# mainV2.net
KiCad netlist of a schematic drawn in Altium Designer
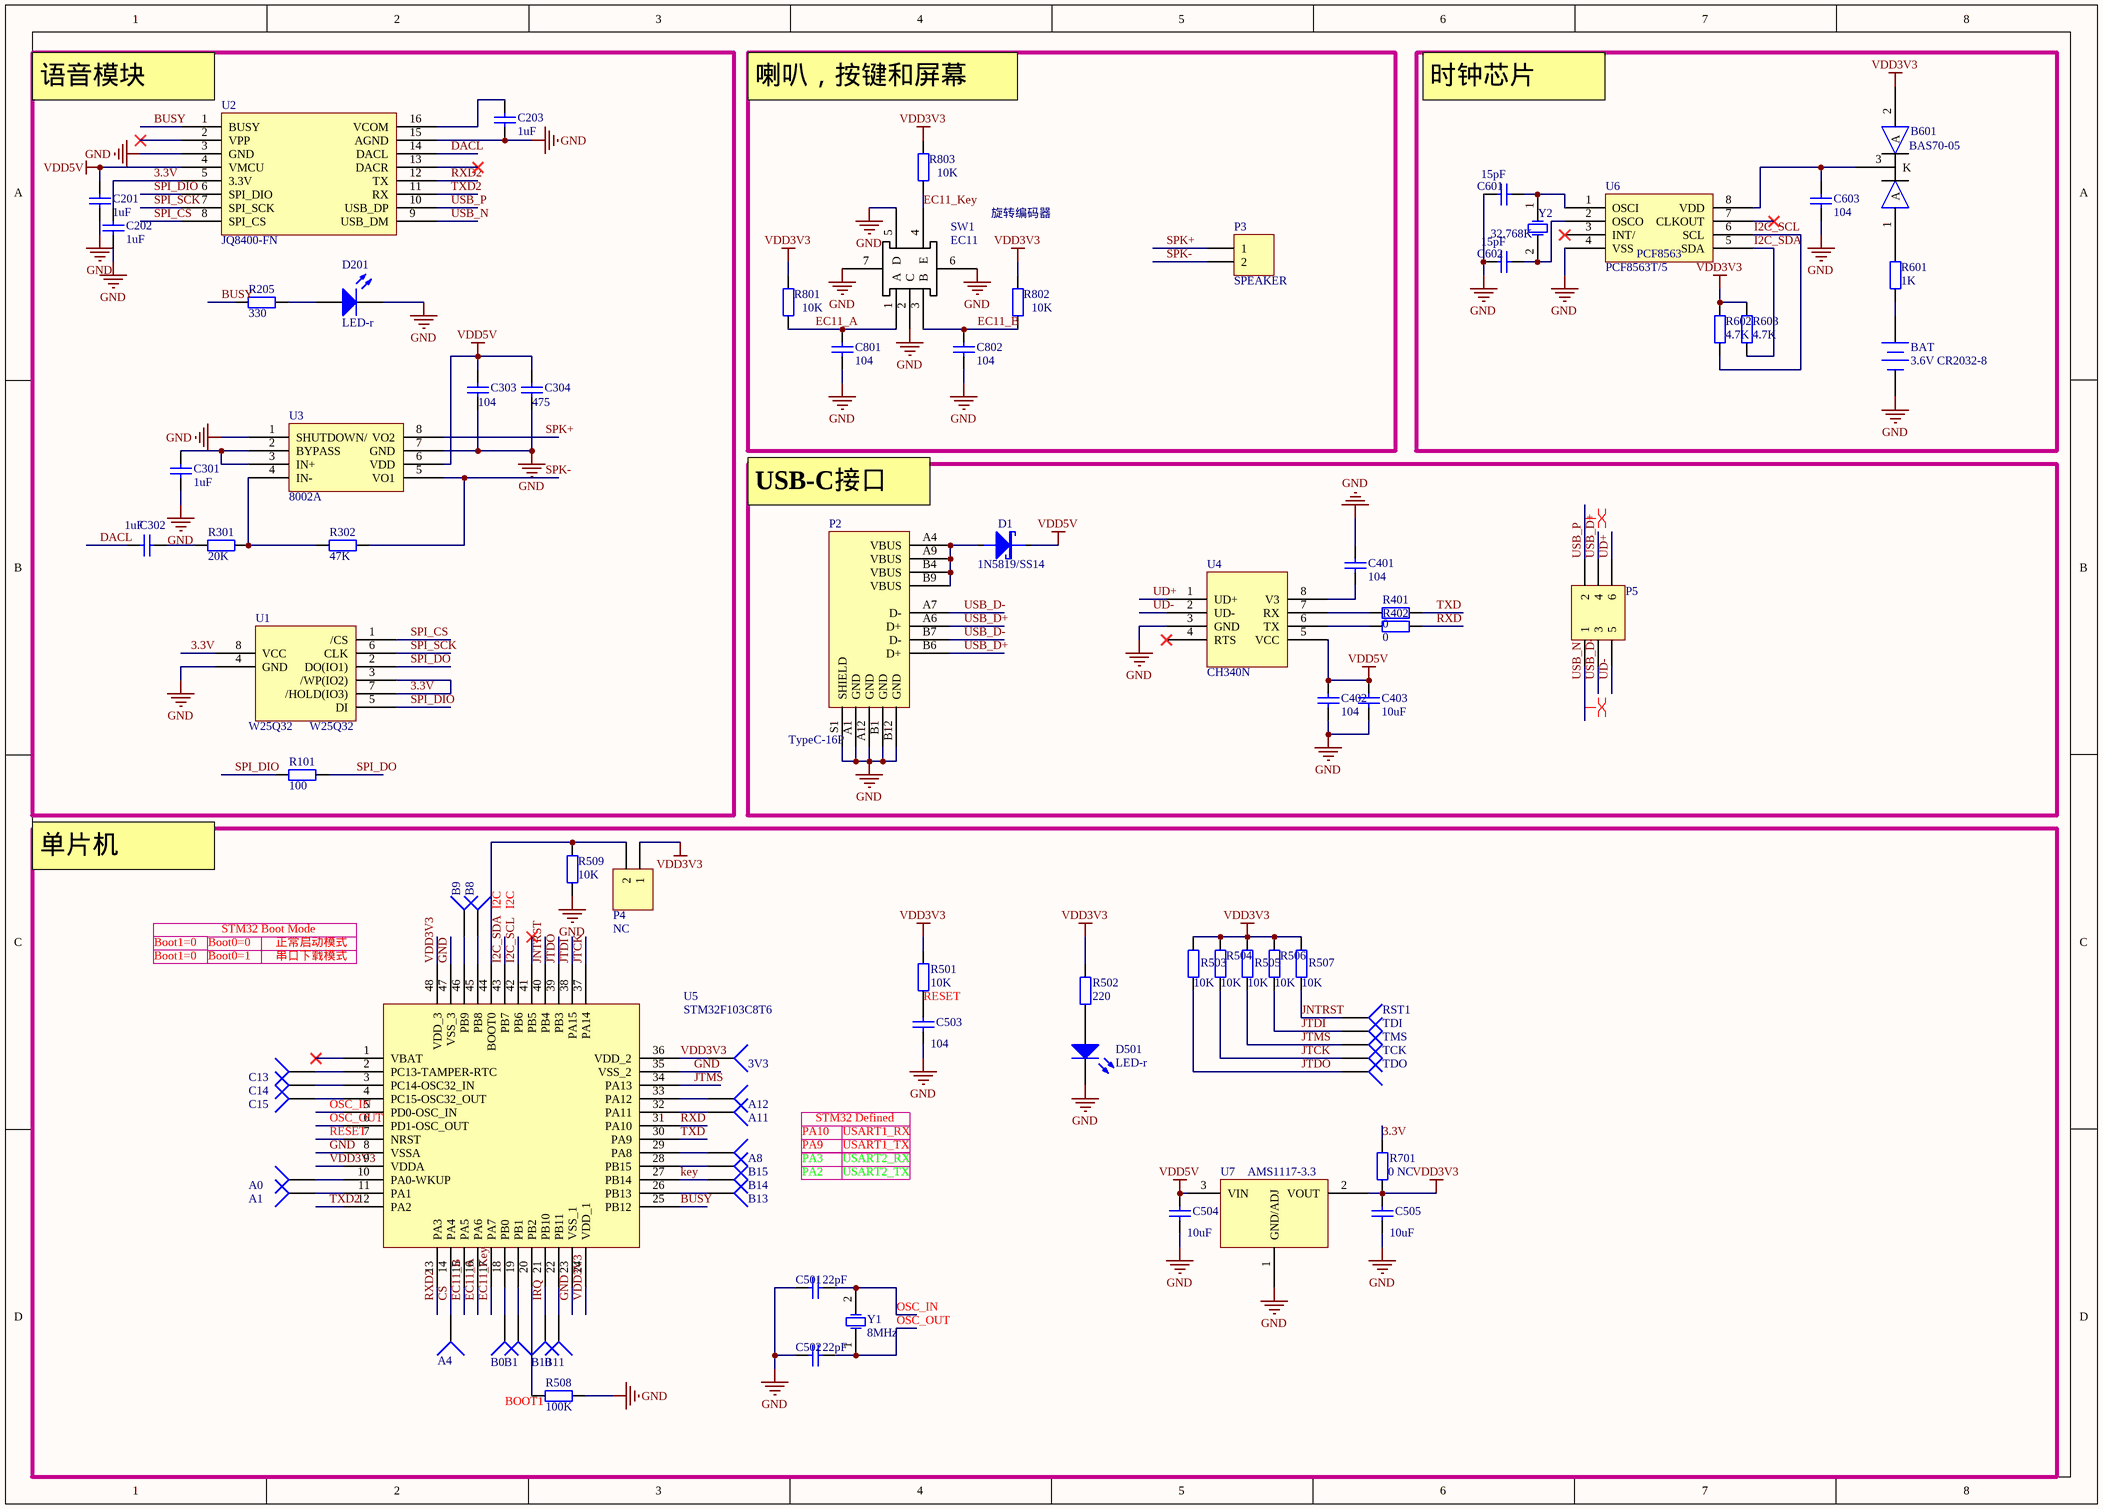
[diagram p0: mainV2.SchDoc]

(export (version "E")
  (design (tool "Eeschema 10.0.6"))
  (components
    (comp (ref "3V3")
      (value "Socket")
      (footprint "TP")
      (fields (field (name "PUBLISHER") "Altium Limited"))
      (libsource (lib "Miscellaneous Connectors") (part "Socket"))
    )
    (comp (ref "A0")
      (value "Socket")
      (footprint "TP")
      (fields (field (name "PUBLISHER") "Altium Limited"))
      (libsource (lib "Miscellaneous Connectors") (part "Socket"))
    )
    (comp (ref "A1")
      (value "Socket")
      (footprint "TP")
      (fields (field (name "PUBLISHER") "Altium Limited"))
      (libsource (lib "Miscellaneous Connectors") (part "Socket"))
    )
    (comp (ref "A4")
      (value "Socket")
      (footprint "TP")
      (fields (field (name "PUBLISHER") "Altium Limited"))
      (libsource (lib "Miscellaneous Connectors") (part "Socket"))
    )
    (comp (ref "A8")
      (value "Socket")
      (footprint "TP")
      (fields (field (name "PUBLISHER") "Altium Limited"))
      (libsource (lib "Miscellaneous Connectors") (part "Socket"))
    )
    (comp (ref "A11")
      (value "Socket")
      (footprint "TP")
      (fields (field (name "PUBLISHER") "Altium Limited"))
      (libsource (lib "Miscellaneous Connectors") (part "Socket"))
    )
    (comp (ref "A12")
      (value "Socket")
      (footprint "TP")
      (fields (field (name "PUBLISHER") "Altium Limited"))
      (libsource (lib "Miscellaneous Connectors") (part "Socket"))
    )
    (comp (ref "B0")
      (value "Socket")
      (footprint "TP")
      (fields (field (name "PUBLISHER") "Altium Limited"))
      (libsource (lib "Miscellaneous Connectors") (part "Socket"))
    )
    (comp (ref "B1")
      (value "Socket")
      (footprint "TP")
      (fields (field (name "PUBLISHER") "Altium Limited"))
      (libsource (lib "Miscellaneous Connectors") (part "Socket"))
    )
    (comp (ref "B8")
      (value "Socket")
      (footprint "TP")
      (fields (field (name "PUBLISHER") "Altium Limited"))
      (libsource (lib "Miscellaneous Connectors") (part "Socket"))
    )
    (comp (ref "B9")
      (value "Socket")
      (footprint "TP")
      (fields (field (name "PUBLISHER") "Altium Limited"))
      (libsource (lib "Miscellaneous Connectors") (part "Socket"))
    )
    (comp (ref "B10")
      (value "Socket")
      (footprint "TP")
      (fields (field (name "PUBLISHER") "Altium Limited"))
      (libsource (lib "Miscellaneous Connectors") (part "Socket"))
    )
    (comp (ref "B11")
      (value "Socket")
      (footprint "TP")
      (fields (field (name "PUBLISHER") "Altium Limited"))
      (libsource (lib "Miscellaneous Connectors") (part "Socket"))
    )
    (comp (ref "B13")
      (value "Socket")
      (footprint "TP")
      (fields (field (name "PUBLISHER") "Altium Limited"))
      (libsource (lib "Miscellaneous Connectors") (part "Socket"))
    )
    (comp (ref "B14")
      (value "Socket")
      (footprint "TP")
      (fields (field (name "PUBLISHER") "Altium Limited"))
      (libsource (lib "Miscellaneous Connectors") (part "Socket"))
    )
    (comp (ref "B15")
      (value "Socket")
      (footprint "TP")
      (fields (field (name "PUBLISHER") "Altium Limited"))
      (libsource (lib "Miscellaneous Connectors") (part "Socket"))
    )
    (comp (ref "B601")
      (value "BAS70-05")
      (footprint "SMT_TRIODE_NPN")
      (description "贴片三极管  丝印75")
      (libsource (lib "Hardware") (part "BAS70 74"))
    )
    (comp (ref "BAT")
      (value "3.6V CR2032-8")
      (footprint "CR2032-8")
      (description "电池座 半圆形")
      (fields (field (name "PUBLISHER") "Altium Limited"))
      (libsource (lib "Miscellaneous Devices") (part "Battery"))
    )
    (comp (ref "C13")
      (value "Socket")
      (footprint "TP")
      (fields (field (name "PUBLISHER") "Altium Limited"))
      (libsource (lib "Miscellaneous Connectors") (part "Socket"))
    )
    (comp (ref "C14")
      (value "Socket")
      (footprint "TP")
      (fields (field (name "PUBLISHER") "Altium Limited"))
      (libsource (lib "Miscellaneous Connectors") (part "Socket"))
    )
    (comp (ref "C15")
      (value "Socket")
      (footprint "TP")
      (fields (field (name "PUBLISHER") "Altium Limited"))
      (libsource (lib "Miscellaneous Connectors") (part "Socket"))
    )
    (comp (ref "C201")
      (value "1uF")
      (footprint "0603_CAP")
      (description "Capacitor 0603")
      (fields (field (name "PUBLISHER") "Altium Limited"))
      (libsource (lib "Miscellaneous Devices") (part "Cap"))
    )
    (comp (ref "C202")
      (value "1uF")
      (footprint "0603_CAP")
      (description "Capacitor 0603")
      (fields (field (name "PUBLISHER") "Altium Limited"))
      (libsource (lib "Miscellaneous Devices") (part "Cap"))
    )
    (comp (ref "C203")
      (value "1uF")
      (footprint "0603_CAP")
      (description "Capacitor 0603")
      (fields (field (name "PUBLISHER") "Altium Limited"))
      (libsource (lib "Miscellaneous Devices") (part "Cap"))
    )
    (comp (ref "C301")
      (value "1uF")
      (footprint "0603_CAP")
      (description "Capacitor 0603")
      (fields (field (name "PUBLISHER") "Altium Limited"))
      (libsource (lib "Miscellaneous Devices") (part "Cap"))
    )
    (comp (ref "C302")
      (value "1uF")
      (footprint "0603_CAP")
      (description "Capacitor 0603")
      (fields (field (name "PUBLISHER") "Altium Limited"))
      (libsource (lib "Miscellaneous Devices") (part "Cap"))
    )
    (comp (ref "C303")
      (value "104")
      (footprint "0603_CAP")
      (description "Capacitor 0603")
      (fields (field (name "PUBLISHER") "Altium Limited"))
      (libsource (lib "Miscellaneous Devices") (part "Cap"))
    )
    (comp (ref "C304")
      (value "475")
      (footprint "0603_CAP")
      (description "Capacitor 0603")
      (fields (field (name "PUBLISHER") "Altium Limited"))
      (libsource (lib "Miscellaneous Devices") (part "Cap"))
    )
    (comp (ref "C401")
      (value "104")
      (footprint "0603_CAP")
      (description "Capacitor 0603")
      (fields (field (name "PUBLISHER") "Altium Limited"))
      (libsource (lib "Miscellaneous Devices") (part "Cap"))
    )
    (comp (ref "C402")
      (value "104")
      (footprint "0603_CAP")
      (description "Capacitor 0603")
      (fields (field (name "PUBLISHER") "Altium Limited"))
      (libsource (lib "Miscellaneous Devices") (part "Cap"))
    )
    (comp (ref "C403")
      (value "10uF")
      (footprint "0603_CAP")
      (description "Capacitor 0603")
      (fields (field (name "PUBLISHER") "Altium Limited"))
      (libsource (lib "Miscellaneous Devices") (part "Cap"))
    )
    (comp (ref "C501")
      (value "22pF")
      (footprint "0603_CAP")
      (description "Capacitor 0603")
      (fields (field (name "PUBLISHER") "Altium Limited"))
      (libsource (lib "Miscellaneous Devices") (part "Cap"))
    )
    (comp (ref "C502")
      (value "22pF")
      (footprint "0603_CAP")
      (description "Capacitor 0603")
      (fields (field (name "PUBLISHER") "Altium Limited"))
      (libsource (lib "Miscellaneous Devices") (part "Cap"))
    )
    (comp (ref "C503")
      (value "104")
      (footprint "0603_CAP")
      (description "Capacitor 0603")
      (fields (field (name "PUBLISHER") "Altium Limited"))
      (libsource (lib "Miscellaneous Devices") (part "Cap"))
    )
    (comp (ref "C504")
      (value "10uF")
      (footprint "0603_CAP")
      (description "Capacitor 0603")
      (fields (field (name "PUBLISHER") "Altium Limited"))
      (libsource (lib "Miscellaneous Devices") (part "Cap"))
    )
    (comp (ref "C505")
      (value "10uF")
      (footprint "0603_CAP")
      (description "Capacitor 0603")
      (fields (field (name "PUBLISHER") "Altium Limited"))
      (libsource (lib "Miscellaneous Devices") (part "Cap"))
    )
    (comp (ref "C601")
      (value "15pF")
      (footprint "0603_CAP")
      (description "Capacitor 0603")
      (fields (field (name "PUBLISHER") "Altium Limited"))
      (libsource (lib "Miscellaneous Devices") (part "Cap"))
    )
    (comp (ref "C602")
      (value "15pF")
      (footprint "0603_CAP")
      (description "Capacitor 0603")
      (fields (field (name "PUBLISHER") "Altium Limited"))
      (libsource (lib "Miscellaneous Devices") (part "Cap"))
    )
    (comp (ref "C603")
      (value "104")
      (footprint "0603_CAP")
      (description "Capacitor 0603")
      (fields (field (name "PUBLISHER") "Altium Limited"))
      (libsource (lib "Miscellaneous Devices") (part "Cap"))
    )
    (comp (ref "C801")
      (value "104")
      (footprint "0603_CAP")
      (description "Capacitor 0603")
      (fields (field (name "PUBLISHER") "Altium Limited"))
      (libsource (lib "Miscellaneous Devices") (part "Cap"))
    )
    (comp (ref "C802")
      (value "104")
      (footprint "0603_CAP")
      (description "Capacitor 0603")
      (fields (field (name "PUBLISHER") "Altium Limited"))
      (libsource (lib "Miscellaneous Devices") (part "Cap"))
    )
    (comp (ref "D1")
      (value "1N5819/SS14")
      (footprint "SMA")
      (description "肖特基整流二极管SOD-323")
      (libsource (lib "Vowstar_Basic_Device") (part "SMT_DIODE_SCHOTTKY_SOD_323"))
    )
    (comp (ref "D201")
      (value "LED-r")
      (footprint "LED-0603")
      (description "NC")
      (fields (field (name "PUBLISHER") "Altium Limited"))
      (libsource (lib "Miscellaneous Devices") (part "LED2"))
    )
    (comp (ref "D501")
      (value "LED-r")
      (footprint "LED-0603")
      (description "NC")
      (fields (field (name "PUBLISHER") "Altium Limited"))
      (libsource (lib "Miscellaneous Devices") (part "LED2"))
    )
    (comp (ref "P2")
      (value "TypeC-16P")
      (footprint "type-c 16pin")
      (libsource (lib "Hardware") (part "TypeC-16P"))
    )
    (comp (ref "P3")
      (value "SPEAKER")
      (footprint "Speaker")
      (description "扬声器")
      (fields (field (name "PUBLISHER") "Altium Limited"))
      (libsource (lib "") (part "Header 2_1"))
    )
    (comp (ref "P4")
      (value "NC")
      (footprint "HDR1X2")
      (description "下载短接口")
      (fields (field (name "PUBLISHER") "Altium Limited"))
      (libsource (lib "Miscellaneous Connectors") (part "Header 2"))
    )
    (comp (ref "P5")
      (value "NC 3X2")
      (footprint "HDR2X3")
      (description "USB跳线接口")
      (fields (field (name "PUBLISHER") "Altium Limited"))
      (libsource (lib "Miscellaneous Connectors") (part "Header 3X2"))
    )
    (comp (ref "R101")
      (value "100")
      (footprint "0603_CAP")
      (description "Resistor 0603")
      (fields (field (name "PUBLISHER") "Altium Limited"))
      (libsource (lib "") (part "Res2_1"))
    )
    (comp (ref "R205")
      (value "330")
      (footprint "0603_CAP")
      (description "Resistor 0603")
      (fields (field (name "PUBLISHER") "Altium Limited"))
      (libsource (lib "") (part "Res2_1"))
    )
    (comp (ref "R301")
      (value "20K")
      (footprint "0603_CAP")
      (description "Resistor 0603")
      (fields (field (name "PUBLISHER") "Altium Limited"))
      (libsource (lib "") (part "Res2_1"))
    )
    (comp (ref "R302")
      (value "47K")
      (footprint "0603_CAP")
      (description "Resistor 0603")
      (fields (field (name "PUBLISHER") "Altium Limited"))
      (libsource (lib "") (part "Res2_1"))
    )
    (comp (ref "R401")
      (value "0")
      (footprint "0603_CAP")
      (description "Resistor 0603")
      (fields (field (name "PUBLISHER") "Altium Limited"))
      (libsource (lib "") (part "Res2_3"))
    )
    (comp (ref "R402")
      (value "0")
      (footprint "0603_CAP")
      (description "Resistor 0603")
      (fields (field (name "PUBLISHER") "Altium Limited"))
      (libsource (lib "") (part "Res2_3"))
    )
    (comp (ref "R501")
      (value "10K")
      (footprint "0603_CAP")
      (description "Resistor 0603")
      (fields (field (name "PUBLISHER") "Altium Limited"))
      (libsource (lib "") (part "Res2_2"))
    )
    (comp (ref "R502")
      (value "220")
      (footprint "0603_CAP")
      (description "Resistor 0603")
      (fields (field (name "PUBLISHER") "Altium Limited"))
      (libsource (lib "") (part "Res2_2"))
    )
    (comp (ref "R503")
      (value "10K")
      (footprint "0603_CAP")
      (description "Resistor 0603")
      (fields (field (name "PUBLISHER") "Altium Limited"))
      (libsource (lib "") (part "Res2_2"))
    )
    (comp (ref "R504")
      (value "10K")
      (footprint "0603_CAP")
      (description "Resistor 0603")
      (fields (field (name "PUBLISHER") "Altium Limited"))
      (libsource (lib "") (part "Res2_2"))
    )
    (comp (ref "R505")
      (value "10K")
      (footprint "0603_CAP")
      (description "Resistor 0603")
      (fields (field (name "PUBLISHER") "Altium Limited"))
      (libsource (lib "") (part "Res2_2"))
    )
    (comp (ref "R506")
      (value "10K")
      (footprint "0603_CAP")
      (description "Resistor 0603")
      (fields (field (name "PUBLISHER") "Altium Limited"))
      (libsource (lib "") (part "Res2_2"))
    )
    (comp (ref "R507")
      (value "10K")
      (footprint "0603_CAP")
      (description "Resistor 0603")
      (fields (field (name "PUBLISHER") "Altium Limited"))
      (libsource (lib "") (part "Res2_2"))
    )
    (comp (ref "R508")
      (value "100K")
      (footprint "0603_CAP")
      (description "Resistor 0603")
      (fields (field (name "PUBLISHER") "Altium Limited"))
      (libsource (lib "") (part "Res2_3"))
    )
    (comp (ref "R509")
      (value "10K")
      (footprint "0603_CAP")
      (description "Resistor 0603")
      (fields (field (name "PUBLISHER") "Altium Limited"))
      (libsource (lib "") (part "Res2_2"))
    )
    (comp (ref "R601")
      (value "1K")
      (footprint "0603_CAP")
      (description "Resistor 0603")
      (fields (field (name "PUBLISHER") "Altium Limited"))
      (libsource (lib "") (part "Res2_2"))
    )
    (comp (ref "R602")
      (value "4.7K")
      (footprint "0603_CAP")
      (description "Resistor 0603")
      (fields (field (name "PUBLISHER") "Altium Limited"))
      (libsource (lib "") (part "Res2_2"))
    )
    (comp (ref "R603")
      (value "4.7K")
      (footprint "0603_CAP")
      (description "Resistor 0603")
      (fields (field (name "PUBLISHER") "Altium Limited"))
      (libsource (lib "") (part "Res2_2"))
    )
    (comp (ref "R701")
      (value "0 NC")
      (footprint "0603_CAP")
      (description "Resistor 0603")
      (fields (field (name "PUBLISHER") "Altium Limited"))
      (libsource (lib "") (part "Res2_2"))
    )
    (comp (ref "R801")
      (value "10K")
      (footprint "0603_CAP")
      (description "Resistor 0603")
      (fields (field (name "PUBLISHER") "Altium Limited"))
      (libsource (lib "Miscellaneous Devices") (part "Res2"))
    )
    (comp (ref "R802")
      (value "10K")
      (footprint "0603_CAP")
      (description "Resistor 0603")
      (fields (field (name "PUBLISHER") "Altium Limited"))
      (libsource (lib "Miscellaneous Devices") (part "Res2"))
    )
    (comp (ref "R803")
      (value "10K")
      (footprint "0603_CAP")
      (description "Resistor 0603")
      (fields (field (name "PUBLISHER") "Altium Limited"))
      (libsource (lib "Miscellaneous Devices") (part "Res2"))
    )
    (comp (ref "RST1")
      (value "Socket")
      (footprint "TP")
      (fields (field (name "PUBLISHER") "Altium Limited"))
      (libsource (lib "Miscellaneous Connectors") (part "Socket"))
    )
    (comp (ref "SW1")
      (value "EC11")
      (footprint "EC11")
      (description "旋转编码器20脉冲")
      (libsource (lib "Hardware") (part "EC11"))
    )
    (comp (ref "TCK")
      (value "Socket")
      (footprint "TP")
      (fields (field (name "PUBLISHER") "Altium Limited"))
      (libsource (lib "Miscellaneous Connectors") (part "Socket"))
    )
    (comp (ref "TDI")
      (value "Socket")
      (footprint "TP")
      (fields (field (name "PUBLISHER") "Altium Limited"))
      (libsource (lib "Miscellaneous Connectors") (part "Socket"))
    )
    (comp (ref "TDO")
      (value "Socket")
      (footprint "TP")
      (fields (field (name "PUBLISHER") "Altium Limited"))
      (libsource (lib "Miscellaneous Connectors") (part "Socket"))
    )
    (comp (ref "TMS")
      (value "Socket")
      (footprint "TP")
      (fields (field (name "PUBLISHER") "Altium Limited"))
      (libsource (lib "Miscellaneous Connectors") (part "Socket"))
    )
    (comp (ref "U1")
      (value "W25Q32")
      (footprint "SOP8-208mil")
      (description "Flash")
      (libsource (lib "Hardware") (part "W25Q32"))
    )
    (comp (ref "U2")
      (value "JQ8400-FN")
      (footprint "JQF8400-FL")
      (libsource (lib "Hardware") (part "JQ8400-FN"))
    )
    (comp (ref "U3")
      (value "8002A")
      (footprint "8002A")
      (description "3W功放")
      (libsource (lib "Hardware") (part "8002A"))
    )
    (comp (ref "U4")
      (value "CH340N")
      (footprint "SOP8")
      (description "U转串")
      (libsource (lib "clock") (part "ch340"))
    )
    (comp (ref "U5")
      (value "STM32F103C8T6")
      (footprint "LQFP48")
      (description "单片机")
      (libsource (lib "Hardware") (part "STM32F101CB"))
    )
    (comp (ref "U6")
      (value "PCF8563T/5")
      (footprint "PCF8563")
      (description "时钟芯片")
      (libsource (lib "Hardware") (part "PCF8563"))
    )
    (comp (ref "U7")
      (value "AMS1117-3.3")
      (footprint "SOT-223")
      (libsource (lib "Vowstar_IC_General") (part "NCP1117"))
    )
    (comp (ref "Y1")
      (value "8MHz")
      (footprint "HC-49SMD")
      (description "49S型直插无源晶振")
      (fields (field (name "PUBLISHER") "Altium Limited"))
      (libsource (lib "Miscellaneous Devices") (part "XTAL"))
    )
    (comp (ref "Y2")
      (value "32.768K")
      (footprint "Crystal")
      (description "圆柱型3*8mm无源晶振")
      (fields (field (name "PUBLISHER") "Altium Limited"))
      (libsource (lib "Miscellaneous Devices") (part "XTAL"))
    )
  )
  (nets
    (net (code "1") (name "/3.3V") (class "Default")
      (node (ref "C202") (pin "2") (pinfunction "2_2") (pintype "passive"))
      (node (ref "R701") (pin "2") (pinfunction "2_2") (pintype "passive"))
      (node (ref "U1") (pin "3") (pinfunction "/WP(IO2)_3") (pintype "passive"))
      (node (ref "U1") (pin "7") (pinfunction "/HOLD(IO3)_7") (pintype "passive"))
      (node (ref "U1") (pin "8") (pinfunction "VCC_8") (pintype "passive"))
      (node (ref "U2") (pin "5") (pinfunction "3.3V_5") (pintype "passive"))
    )
    (net (code "2") (name "/BUSY") (class "Default")
      (node (ref "R205") (pin "2") (pinfunction "2_2") (pintype "passive"))
      (node (ref "U2") (pin "1") (pinfunction "BUSY_1") (pintype "passive"))
      (node (ref "U5") (pin "25") (pinfunction "PB12_25") (pintype "passive"))
    )
    (net (code "3") (name "/CS") (class "Default")
      (node (ref "A4") (pin "1") (pinfunction "1_1") (pintype "passive"))
      (node (ref "U5") (pin "14") (pinfunction "PA4_14") (pintype "passive"))
    )
    (net (code "4") (name "/DACL") (class "Default")
      (node (ref "C302") (pin "2") (pinfunction "2_2") (pintype "passive"))
      (node (ref "U2") (pin "14") (pinfunction "DACL_14") (pintype "passive"))
    )
    (net (code "5") (name "/EC11_A") (class "Default")
      (node (ref "C801") (pin "1") (pinfunction "1_1") (pintype "passive"))
      (node (ref "R801") (pin "2") (pinfunction "2_2") (pintype "passive"))
      (node (ref "SW1") (pin "1") (pinfunction "A_1") (pintype "passive"))
      (node (ref "U5") (pin "16") (pinfunction "PA6_16") (pintype "passive"))
    )
    (net (code "6") (name "/EC11_B") (class "Default")
      (node (ref "C802") (pin "1") (pinfunction "1_1") (pintype "passive"))
      (node (ref "R802") (pin "2") (pinfunction "2_2") (pintype "passive"))
      (node (ref "SW1") (pin "3") (pinfunction "B_3") (pintype "passive"))
      (node (ref "U5") (pin "15") (pinfunction "PA5_15") (pintype "passive"))
    )
    (net (code "7") (name "/EC11_Key") (class "Default")
      (node (ref "R803") (pin "2") (pinfunction "2_2") (pintype "passive"))
      (node (ref "SW1") (pin "4") (pinfunction "E_4") (pintype "passive"))
      (node (ref "U5") (pin "17") (pinfunction "PA7_17") (pintype "passive"))
    )
    (net (code "8") (name "/I2C_SCL") (class "Default")
      (node (ref "R602") (pin "1") (pinfunction "1_1") (pintype "passive"))
      (node (ref "U5") (pin "42") (pinfunction "PB6_42") (pintype "passive"))
      (node (ref "U6") (pin "6") (pinfunction "SCL_6") (pintype "passive"))
    )
    (net (code "9") (name "/I2C_SDA") (class "Default")
      (node (ref "R603") (pin "1") (pinfunction "1_1") (pintype "passive"))
      (node (ref "U5") (pin "43") (pinfunction "PB7_43") (pintype "passive"))
      (node (ref "U6") (pin "5") (pinfunction "SDA_5") (pintype "passive"))
    )
    (net (code "10") (name "/IRQ") (class "Default")
      (node (ref "B10") (pin "1") (pinfunction "1_1") (pintype "passive"))
      (node (ref "U5") (pin "21") (pinfunction "PB10_21") (pintype "passive"))
    )
    (net (code "11") (name "/JNTRST") (class "Default")
      (node (ref "R507") (pin "1") (pinfunction "1_1") (pintype "passive"))
      (node (ref "RST1") (pin "1") (pinfunction "1_1") (pintype "passive"))
      (node (ref "U5") (pin "40") (pinfunction "PB4_40") (pintype "passive"))
    )
    (net (code "12") (name "/JTCK") (class "Default")
      (node (ref "R504") (pin "1") (pinfunction "1_1") (pintype "passive"))
      (node (ref "TCK") (pin "1") (pinfunction "1_1") (pintype "passive"))
      (node (ref "U5") (pin "37") (pinfunction "PA14_37") (pintype "passive"))
    )
    (net (code "13") (name "/JTDI") (class "Default")
      (node (ref "R506") (pin "1") (pinfunction "1_1") (pintype "passive"))
      (node (ref "TDI") (pin "1") (pinfunction "1_1") (pintype "passive"))
      (node (ref "U5") (pin "38") (pinfunction "PA15_38") (pintype "passive"))
    )
    (net (code "14") (name "/JTDO") (class "Default")
      (node (ref "R503") (pin "1") (pinfunction "1_1") (pintype "passive"))
      (node (ref "TDO") (pin "1") (pinfunction "1_1") (pintype "passive"))
      (node (ref "U5") (pin "39") (pinfunction "PB3_39") (pintype "passive"))
    )
    (net (code "15") (name "/JTMS") (class "Default")
      (node (ref "R505") (pin "1") (pinfunction "1_1") (pintype "passive"))
      (node (ref "TMS") (pin "1") (pinfunction "1_1") (pintype "passive"))
      (node (ref "U5") (pin "34") (pinfunction "PA13_34") (pintype "passive"))
    )
    (net (code "16") (name "/OSC_IN") (class "Default")
      (node (ref "C501") (pin "1") (pinfunction "1_1") (pintype "passive"))
      (node (ref "U5") (pin "5") (pinfunction "PD0-OSC_IN_5") (pintype "passive"))
      (node (ref "Y1") (pin "2") (pinfunction "OSC2_2") (pintype "passive"))
    )
    (net (code "17") (name "/OSC_OUT") (class "Default")
      (node (ref "C502") (pin "1") (pinfunction "1_1") (pintype "passive"))
      (node (ref "U5") (pin "6") (pinfunction "PD1-OSC_OUT_6") (pintype "passive"))
      (node (ref "Y1") (pin "1") (pinfunction "OSC1_1") (pintype "passive"))
    )
    (net (code "18") (name "/RESET") (class "Default")
      (node (ref "C503") (pin "1") (pinfunction "1_1") (pintype "passive"))
      (node (ref "R501") (pin "1") (pinfunction "1_1") (pintype "passive"))
      (node (ref "U5") (pin "7") (pinfunction "NRST_7") (pintype "passive"))
    )
    (net (code "19") (name "/RXD") (class "Default")
      (node (ref "R402") (pin "2") (pinfunction "2_2") (pintype "passive"))
      (node (ref "U5") (pin "31") (pinfunction "PA10_31") (pintype "passive"))
    )
    (net (code "20") (name "/RXD2") (class "Default")
      (node (ref "U2") (pin "12") (pinfunction "TX_12") (pintype "passive"))
      (node (ref "U5") (pin "13") (pinfunction "PA3_13") (pintype "passive"))
    )
    (net (code "21") (name "/SPI_CS") (class "Default")
      (node (ref "U1") (pin "1") (pinfunction "/CS_1") (pintype "passive"))
      (node (ref "U2") (pin "8") (pinfunction "SPI_CS_8") (pintype "passive"))
    )
    (net (code "22") (name "/SPI_DIO") (class "Default")
      (node (ref "R101") (pin "2") (pinfunction "2_2") (pintype "passive"))
      (node (ref "U1") (pin "5") (pinfunction "DI_5") (pintype "passive"))
      (node (ref "U2") (pin "6") (pinfunction "SPI_DIO_6") (pintype "passive"))
    )
    (net (code "23") (name "/SPI_DO") (class "Default")
      (node (ref "R101") (pin "1") (pinfunction "1_1") (pintype "passive"))
      (node (ref "U1") (pin "2") (pinfunction "DO(IO1)_2") (pintype "passive"))
    )
    (net (code "24") (name "/SPI_SCK") (class "Default")
      (node (ref "U1") (pin "6") (pinfunction "CLK_6") (pintype "passive"))
      (node (ref "U2") (pin "7") (pinfunction "SPI_SCK_7") (pintype "passive"))
    )
    (net (code "25") (name "/SPK+") (class "Default")
      (node (ref "P3") (pin "1") (pinfunction "1_1") (pintype "passive"))
      (node (ref "U3") (pin "8") (pinfunction "VO2_8") (pintype "passive"))
    )
    (net (code "26") (name "/SPK-") (class "Default")
      (node (ref "P3") (pin "2") (pinfunction "2_2") (pintype "passive"))
      (node (ref "R302") (pin "1") (pinfunction "1_1") (pintype "passive"))
      (node (ref "U3") (pin "5") (pinfunction "VO1_5") (pintype "passive"))
    )
    (net (code "27") (name "/TXD") (class "Default")
      (node (ref "R401") (pin "2") (pinfunction "2_2") (pintype "passive"))
      (node (ref "U5") (pin "30") (pinfunction "PA9_30") (pintype "passive"))
    )
    (net (code "28") (name "/TXD2") (class "Default")
      (node (ref "U2") (pin "11") (pinfunction "RX_11") (pintype "passive"))
      (node (ref "U5") (pin "12") (pinfunction "PA2_12") (pintype "passive"))
    )
    (net (code "29") (name "/UD+") (class "Default")
      (node (ref "P5") (pin "6") (pinfunction "6_6") (pintype "passive"))
      (node (ref "U4") (pin "1") (pinfunction "UD+_1") (pintype "passive"))
    )
    (net (code "30") (name "/UD-") (class "Default")
      (node (ref "P5") (pin "5") (pinfunction "5_5") (pintype "passive"))
      (node (ref "U4") (pin "2") (pinfunction "UD-_2") (pintype "passive"))
    )
    (net (code "31") (name "/USB_D+") (class "Default")
      (node (ref "P2") (pin "A6") (pinfunction "D+_A6") (pintype "passive"))
      (node (ref "P2") (pin "B6") (pinfunction "D+_B6") (pintype "passive"))
      (node (ref "P5") (pin "4") (pinfunction "4_4") (pintype "passive"))
    )
    (net (code "32") (name "/USB_D-") (class "Default")
      (node (ref "P2") (pin "A7") (pinfunction "D-_A7") (pintype "passive"))
      (node (ref "P2") (pin "B7") (pinfunction "D-_B7") (pintype "passive"))
      (node (ref "P5") (pin "3") (pinfunction "3_3") (pintype "passive"))
    )
    (net (code "33") (name "/USB_N") (class "Default")
      (node (ref "P5") (pin "1") (pinfunction "1_1") (pintype "passive"))
      (node (ref "U2") (pin "9") (pinfunction "USB_DM_9") (pintype "passive"))
    )
    (net (code "34") (name "/USB_P") (class "Default")
      (node (ref "P5") (pin "2") (pinfunction "2_2") (pintype "passive"))
      (node (ref "U2") (pin "10") (pinfunction "USB_DP_10") (pintype "passive"))
    )
    (net (code "35") (name "/key") (class "Default")
      (node (ref "B14") (pin "1") (pinfunction "1_1") (pintype "passive"))
      (node (ref "U5") (pin "27") (pinfunction "PB14_27") (pintype "passive"))
    )
    (net (code "36") (name "GND") (class "Default")
      (node (ref "BAT") (pin "2") (pinfunction "-_2") (pintype "passive"))
      (node (ref "C201") (pin "1") (pinfunction "1_1") (pintype "passive"))
      (node (ref "C202") (pin "1") (pinfunction "1_1") (pintype "passive"))
      (node (ref "C203") (pin "2") (pinfunction "2_2") (pintype "passive"))
      (node (ref "C301") (pin "1") (pinfunction "1_1") (pintype "passive"))
      (node (ref "C303") (pin "2") (pinfunction "2_2") (pintype "passive"))
      (node (ref "C304") (pin "2") (pinfunction "2_2") (pintype "passive"))
      (node (ref "C401") (pin "2") (pinfunction "2_2") (pintype "passive"))
      (node (ref "C402") (pin "1") (pinfunction "1_1") (pintype "passive"))
      (node (ref "C403") (pin "1") (pinfunction "1_1") (pintype "passive"))
      (node (ref "C501") (pin "2") (pinfunction "2_2") (pintype "passive"))
      (node (ref "C502") (pin "2") (pinfunction "2_2") (pintype "passive"))
      (node (ref "C503") (pin "2") (pinfunction "2_2") (pintype "passive"))
      (node (ref "C504") (pin "2") (pinfunction "2_2") (pintype "passive"))
      (node (ref "C505") (pin "2") (pinfunction "2_2") (pintype "passive"))
      (node (ref "C601") (pin "2") (pinfunction "2_2") (pintype "passive"))
      (node (ref "C602") (pin "2") (pinfunction "2_2") (pintype "passive"))
      (node (ref "C603") (pin "2") (pinfunction "2_2") (pintype "passive"))
      (node (ref "C801") (pin "2") (pinfunction "2_2") (pintype "passive"))
      (node (ref "C802") (pin "2") (pinfunction "2_2") (pintype "passive"))
      (node (ref "D201") (pin "2") (pinfunction "K_2") (pintype "passive"))
      (node (ref "D501") (pin "2") (pinfunction "K_2") (pintype "passive"))
      (node (ref "P2") (pin "A1") (pinfunction "GND_A1") (pintype "passive"))
      (node (ref "P2") (pin "A12") (pinfunction "GND_A12") (pintype "passive"))
      (node (ref "P2") (pin "B1") (pinfunction "GND_B1") (pintype "passive"))
      (node (ref "P2") (pin "B12") (pinfunction "GND_B12") (pintype "passive"))
      (node (ref "P2") (pin "S1") (pinfunction "SHIELD_S1") (pintype "passive"))
      (node (ref "R508") (pin "2") (pinfunction "2_2") (pintype "passive"))
      (node (ref "R509") (pin "1") (pinfunction "1_1") (pintype "passive"))
      (node (ref "SW1") (pin "2") (pinfunction "C_2") (pintype "passive"))
      (node (ref "SW1") (pin "5") (pinfunction "D_5") (pintype "passive"))
      (node (ref "SW1") (pin "6") (pinfunction "6_6") (pintype "passive"))
      (node (ref "SW1") (pin "7") (pinfunction "7_7") (pintype "passive"))
      (node (ref "U1") (pin "4") (pinfunction "GND_4") (pintype "passive"))
      (node (ref "U2") (pin "15") (pinfunction "AGND_15") (pintype "passive"))
      (node (ref "U2") (pin "3") (pinfunction "GND_3") (pintype "passive"))
      (node (ref "U3") (pin "1") (pinfunction "SHUTDOWN/_1") (pintype "passive"))
      (node (ref "U3") (pin "7") (pinfunction "GND_7") (pintype "passive"))
      (node (ref "U4") (pin "3") (pinfunction "GND_3") (pintype "passive"))
      (node (ref "U5") (pin "23") (pinfunction "VSS_1_23") (pintype "passive"))
      (node (ref "U5") (pin "35") (pinfunction "VSS_2_35") (pintype "passive"))
      (node (ref "U5") (pin "47") (pinfunction "VSS_3_47") (pintype "passive"))
      (node (ref "U5") (pin "8") (pinfunction "VSSA_8") (pintype "passive"))
      (node (ref "U6") (pin "4") (pinfunction "VSS_4") (pintype "passive"))
      (node (ref "U7") (pin "1") (pinfunction "GND/ADJ_1") (pintype "passive"))
    )
    (net (code "37") (name "Net-(B601-A-Pad1)") (class "Default")
      (node (ref "B601") (pin "1") (pinfunction "A_1") (pintype "passive"))
      (node (ref "R601") (pin "2") (pinfunction "2_2") (pintype "passive"))
    )
    (net (code "38") (name "Net-(B601-K)") (class "Default")
      (node (ref "B601") (pin "3") (pinfunction "K_3") (pintype "passive"))
      (node (ref "C603") (pin "1") (pinfunction "1_1") (pintype "passive"))
      (node (ref "U6") (pin "8") (pinfunction "VDD_8") (pintype "passive"))
    )
    (net (code "39") (name "Net-(BAT-+)") (class "Default")
      (node (ref "BAT") (pin "1") (pinfunction "+_1") (pintype "passive"))
      (node (ref "R601") (pin "1") (pinfunction "1_1") (pintype "passive"))
    )
    (net (code "40") (name "Net-(C302-Pad1)") (class "Default")
      (node (ref "C302") (pin "1") (pinfunction "1_1") (pintype "passive"))
      (node (ref "R301") (pin "2") (pinfunction "2_2") (pintype "passive"))
    )
    (net (code "41") (name "Net-(D1-A)") (class "Default")
      (node (ref "D1") (pin "1") (pinfunction "A_1") (pintype "passive"))
      (node (ref "P2") (pin "A4") (pinfunction "VBUS_A4") (pintype "passive"))
      (node (ref "P2") (pin "A9") (pinfunction "VBUS_A9") (pintype "passive"))
      (node (ref "P2") (pin "B4") (pinfunction "VBUS_B4") (pintype "passive"))
      (node (ref "P2") (pin "B9") (pinfunction "VBUS_B9") (pintype "passive"))
    )
    (net (code "42") (name "Net-(D201-A)") (class "Default")
      (node (ref "D201") (pin "1") (pinfunction "A_1") (pintype "passive"))
      (node (ref "R205") (pin "1") (pinfunction "1_1") (pintype "passive"))
    )
    (net (code "43") (name "Net-(D501-A)") (class "Default")
      (node (ref "D501") (pin "1") (pinfunction "A_1") (pintype "passive"))
      (node (ref "R502") (pin "1") (pinfunction "1_1") (pintype "passive"))
    )
    (net (code "44") (name "Net-(U2-VCOM)") (class "Default")
      (node (ref "C203") (pin "1") (pinfunction "1_1") (pintype "passive"))
      (node (ref "U2") (pin "16") (pinfunction "VCOM_16") (pintype "passive"))
    )
    (net (code "45") (name "Net-(U3-BYPASS)") (class "Default")
      (node (ref "C301") (pin "2") (pinfunction "2_2") (pintype "passive"))
      (node (ref "U3") (pin "2") (pinfunction "BYPASS_2") (pintype "passive"))
      (node (ref "U3") (pin "3") (pinfunction "IN+_3") (pintype "passive"))
    )
    (net (code "46") (name "Net-(U3-IN-)") (class "Default")
      (node (ref "R301") (pin "1") (pinfunction "1_1") (pintype "passive"))
      (node (ref "R302") (pin "2") (pinfunction "2_2") (pintype "passive"))
      (node (ref "U3") (pin "4") (pinfunction "IN-_4") (pintype "passive"))
    )
    (net (code "47") (name "Net-(U4-RX)") (class "Default")
      (node (ref "R401") (pin "1") (pinfunction "1_1") (pintype "passive"))
      (node (ref "U4") (pin "7") (pinfunction "RX_7") (pintype "passive"))
    )
    (net (code "48") (name "Net-(U4-TX)") (class "Default")
      (node (ref "R402") (pin "1") (pinfunction "1_1") (pintype "passive"))
      (node (ref "U4") (pin "6") (pinfunction "TX_6") (pintype "passive"))
    )
    (net (code "49") (name "Net-(U4-V3)") (class "Default")
      (node (ref "C401") (pin "1") (pinfunction "1_1") (pintype "passive"))
      (node (ref "U4") (pin "8") (pinfunction "V3_8") (pintype "passive"))
    )
    (net (code "50") (name "Net-(U5-BOOT0)") (class "Default")
      (node (ref "P4") (pin "2") (pinfunction "2_2") (pintype "passive"))
      (node (ref "R509") (pin "2") (pinfunction "2_2") (pintype "passive"))
      (node (ref "U5") (pin "44") (pinfunction "BOOT0_44") (pintype "passive"))
    )
    (net (code "51") (name "Net-(U5-PA0-WKUP)") (class "Default")
      (node (ref "A0") (pin "1") (pinfunction "1_1") (pintype "passive"))
      (node (ref "U5") (pin "10") (pinfunction "PA0-WKUP_10") (pintype "passive"))
    )
    (net (code "52") (name "Net-(U5-PA1)") (class "Default")
      (node (ref "A1") (pin "1") (pinfunction "1_1") (pintype "passive"))
      (node (ref "U5") (pin "11") (pinfunction "PA1_11") (pintype "passive"))
    )
    (net (code "53") (name "Net-(U5-PA8)") (class "Default")
      (node (ref "A8") (pin "1") (pinfunction "1_1") (pintype "passive"))
      (node (ref "U5") (pin "29") (pinfunction "PA8_29") (pintype "passive"))
    )
    (net (code "54") (name "Net-(U5-PA11)") (class "Default")
      (node (ref "A11") (pin "1") (pinfunction "1_1") (pintype "passive"))
      (node (ref "U5") (pin "32") (pinfunction "PA11_32") (pintype "passive"))
    )
    (net (code "55") (name "Net-(U5-PA12)") (class "Default")
      (node (ref "A12") (pin "1") (pinfunction "1_1") (pintype "passive"))
      (node (ref "U5") (pin "33") (pinfunction "PA12_33") (pintype "passive"))
    )
    (net (code "56") (name "Net-(U5-PB0)") (class "Default")
      (node (ref "B0") (pin "1") (pinfunction "1_1") (pintype "passive"))
      (node (ref "U5") (pin "18") (pinfunction "PB0_18") (pintype "passive"))
    )
    (net (code "57") (name "Net-(U5-PB1)") (class "Default")
      (node (ref "B1") (pin "1") (pinfunction "1_1") (pintype "passive"))
      (node (ref "U5") (pin "19") (pinfunction "PB1_19") (pintype "passive"))
    )
    (net (code "58") (name "Net-(U5-PB2)") (class "Default")
      (node (ref "R508") (pin "1") (pinfunction "1_1") (pintype "passive"))
      (node (ref "U5") (pin "20") (pinfunction "PB2_20") (pintype "passive"))
    )
    (net (code "59") (name "Net-(U5-PB8)") (class "Default")
      (node (ref "B8") (pin "1") (pinfunction "1_1") (pintype "passive"))
      (node (ref "U5") (pin "45") (pinfunction "PB8_45") (pintype "passive"))
    )
    (net (code "60") (name "Net-(U5-PB9)") (class "Default")
      (node (ref "B9") (pin "1") (pinfunction "1_1") (pintype "passive"))
      (node (ref "U5") (pin "46") (pinfunction "PB9_46") (pintype "passive"))
    )
    (net (code "61") (name "Net-(U5-PB11)") (class "Default")
      (node (ref "B11") (pin "1") (pinfunction "1_1") (pintype "passive"))
      (node (ref "U5") (pin "22") (pinfunction "PB11_22") (pintype "passive"))
    )
    (net (code "62") (name "Net-(U5-PB13)") (class "Default")
      (node (ref "B13") (pin "1") (pinfunction "1_1") (pintype "passive"))
      (node (ref "U5") (pin "26") (pinfunction "PB13_26") (pintype "passive"))
    )
    (net (code "63") (name "Net-(U5-PB15)") (class "Default")
      (node (ref "B15") (pin "1") (pinfunction "1_1") (pintype "passive"))
      (node (ref "U5") (pin "28") (pinfunction "PB15_28") (pintype "passive"))
    )
    (net (code "64") (name "Net-(U5-PC13-TAMPER-RTC)") (class "Default")
      (node (ref "C13") (pin "1") (pinfunction "1_1") (pintype "passive"))
      (node (ref "U5") (pin "2") (pinfunction "PC13-TAMPER-RTC_2") (pintype "passive"))
    )
    (net (code "65") (name "Net-(U5-PC14-OSC32_IN)") (class "Default")
      (node (ref "C14") (pin "1") (pinfunction "1_1") (pintype "passive"))
      (node (ref "U5") (pin "3") (pinfunction "PC14-OSC32_IN_3") (pintype "passive"))
    )
    (net (code "66") (name "Net-(U5-PC15-OSC32_OUT)") (class "Default")
      (node (ref "C15") (pin "1") (pinfunction "1_1") (pintype "passive"))
      (node (ref "U5") (pin "4") (pinfunction "PC15-OSC32_OUT_4") (pintype "passive"))
    )
    (net (code "67") (name "Net-(U6-OSCI)") (class "Default")
      (node (ref "C601") (pin "1") (pinfunction "1_1") (pintype "passive"))
      (node (ref "U6") (pin "1") (pinfunction "OSCI_1") (pintype "passive"))
      (node (ref "Y2") (pin "1") (pinfunction "OSC1_1") (pintype "passive"))
    )
    (net (code "68") (name "Net-(U6-OSCO)") (class "Default")
      (node (ref "C602") (pin "1") (pinfunction "1_1") (pintype "passive"))
      (node (ref "U6") (pin "2") (pinfunction "OSCO_2") (pintype "passive"))
      (node (ref "Y2") (pin "2") (pinfunction "OSC2_2") (pintype "passive"))
    )
    (net (code "69") (name "VDD3V3") (class "Default")
      (node (ref "3V3") (pin "1") (pinfunction "1_1") (pintype "passive"))
      (node (ref "B601") (pin "2") (pinfunction "A_2") (pintype "passive"))
      (node (ref "C505") (pin "1") (pinfunction "1_1") (pintype "passive"))
      (node (ref "P4") (pin "1") (pinfunction "1_1") (pintype "passive"))
      (node (ref "R501") (pin "2") (pinfunction "2_2") (pintype "passive"))
      (node (ref "R502") (pin "2") (pinfunction "2_2") (pintype "passive"))
      (node (ref "R503") (pin "2") (pinfunction "2_2") (pintype "passive"))
      (node (ref "R504") (pin "2") (pinfunction "2_2") (pintype "passive"))
      (node (ref "R505") (pin "2") (pinfunction "2_2") (pintype "passive"))
      (node (ref "R506") (pin "2") (pinfunction "2_2") (pintype "passive"))
      (node (ref "R507") (pin "2") (pinfunction "2_2") (pintype "passive"))
      (node (ref "R602") (pin "2") (pinfunction "2_2") (pintype "passive"))
      (node (ref "R603") (pin "2") (pinfunction "2_2") (pintype "passive"))
      (node (ref "R701") (pin "1") (pinfunction "1_1") (pintype "passive"))
      (node (ref "R801") (pin "1") (pinfunction "1_1") (pintype "passive"))
      (node (ref "R802") (pin "1") (pinfunction "1_1") (pintype "passive"))
      (node (ref "R803") (pin "1") (pinfunction "1_1") (pintype "passive"))
      (node (ref "U5") (pin "24") (pinfunction "VDD_1_24") (pintype "passive"))
      (node (ref "U5") (pin "36") (pinfunction "VDD_2_36") (pintype "passive"))
      (node (ref "U5") (pin "48") (pinfunction "VDD_3_48") (pintype "passive"))
      (node (ref "U5") (pin "9") (pinfunction "VDDA_9") (pintype "passive"))
      (node (ref "U7") (pin "2") (pinfunction "VOUT_2") (pintype "passive"))
    )
    (net (code "70") (name "VDD5V") (class "Default")
      (node (ref "C201") (pin "2") (pinfunction "2_2") (pintype "passive"))
      (node (ref "C303") (pin "1") (pinfunction "1_1") (pintype "passive"))
      (node (ref "C304") (pin "1") (pinfunction "1_1") (pintype "passive"))
      (node (ref "C402") (pin "2") (pinfunction "2_2") (pintype "passive"))
      (node (ref "C403") (pin "2") (pinfunction "2_2") (pintype "passive"))
      (node (ref "C504") (pin "1") (pinfunction "1_1") (pintype "passive"))
      (node (ref "D1") (pin "2") (pinfunction "K_2") (pintype "passive"))
      (node (ref "U2") (pin "4") (pinfunction "VMCU_4") (pintype "passive"))
      (node (ref "U3") (pin "6") (pinfunction "VDD_6") (pintype "passive"))
      (node (ref "U4") (pin "5") (pinfunction "VCC_5") (pintype "passive"))
      (node (ref "U7") (pin "3") (pinfunction "VIN_3") (pintype "passive"))
    )
    (net (code "71") (name "unconnected-(U2-DACR-Pad13)") (class "Default")
      (node (ref "U2") (pin "13") (pinfunction "DACR_13") (pintype "passive+no_connect"))
    )
    (net (code "72") (name "unconnected-(U2-VPP-Pad2)") (class "Default")
      (node (ref "U2") (pin "2") (pinfunction "VPP_2") (pintype "passive+no_connect"))
    )
    (net (code "73") (name "unconnected-(U4-RTS-Pad4)") (class "Default")
      (node (ref "U4") (pin "4") (pinfunction "RTS_4") (pintype "passive+no_connect"))
    )
    (net (code "74") (name "unconnected-(U5-PB5-Pad41)") (class "Default")
      (node (ref "U5") (pin "41") (pinfunction "PB5_41") (pintype "passive+no_connect"))
    )
    (net (code "75") (name "unconnected-(U5-VBAT-Pad1)") (class "Default")
      (node (ref "U5") (pin "1") (pinfunction "VBAT_1") (pintype "passive+no_connect"))
    )
    (net (code "76") (name "unconnected-(U6-CLKOUT-Pad7)") (class "Default")
      (node (ref "U6") (pin "7") (pinfunction "CLKOUT_7") (pintype "passive+no_connect"))
    )
    (net (code "77") (name "unconnected-(U6-INT{slash}-Pad3)") (class "Default")
      (node (ref "U6") (pin "3") (pinfunction "INT/_3") (pintype "passive+no_connect"))
    )
  )
)
